# PuppyLight.net
KiCad netlist of a schematic drawn in Altium Designer
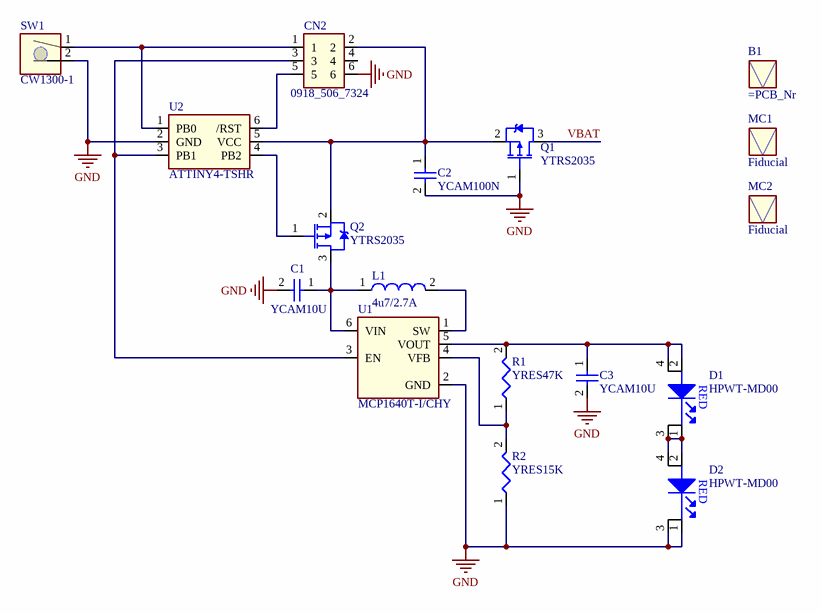
[diagram p0: PuppyLight.SchDoc]

(export (version "E")
  (design (tool "Eeschema 10.0.6"))
  (components
    (comp (ref "B1")
      (value "~")
      (footprint "MC_BoardNr")
      (fields (field (name "PART NUMBER") "BARE_PCB"))
      (libsource (lib "Testing") (part "BD_PCB"))
    )
    (comp (ref "C1") (value "YCAM10U") (footprint "CA_1206") (libsource (lib "Testing") (part "CA_NONPOL")))
    (comp (ref "C2") (value "YCAM100N") (footprint "CA_1206") (libsource (lib "Testing") (part "CA_NONPOL")))
    (comp (ref "C3") (value "YCAM10U") (footprint "CA_1206") (libsource (lib "Testing") (part "CA_NONPOL")))
    (comp (ref "CN2")
      (value "0918_506_7324")
      (footprint "CN_HARTING_918506X324")
      (fields (field (name "MANUFACTURER") "Harting"))
      (libsource (lib "Testing") (part "CN_2x3P"))
    )
    (comp (ref "D1")
      (value "HPWT-MD00")
      (footprint "DI_HPWT_Mx000-00000")
      (fields (field (name "MANUFACTURER") "Lumileds"))
      (libsource (lib "Testing") (part "DI_LED_RED_13_24"))
    )
    (comp (ref "D2")
      (value "HPWT-MD00")
      (footprint "DI_HPWT_Mx000-00000")
      (fields (field (name "MANUFACTURER") "Lumileds"))
      (libsource (lib "Testing") (part "DI_LED_RED_13_24"))
    )
    (comp (ref "L1")
      (value "4u7/2.7A")
      (footprint "CL_STD_2220")
      (fields (field (name "PART NUMBER") "LQH55DN4R7M03L") (field (name "MANUFACTURER") "Murata"))
      (libsource (lib "Testing") (part "CL_COIL"))
    )
    (comp (ref "MC1")
      (value "Fiducial")
      (footprint "MC_FIDUCIAL")
      (libsource (lib "Testing") (part "MC_MechPart_No_BOM"))
    )
    (comp (ref "MC2")
      (value "Fiducial")
      (footprint "MC_FIDUCIAL")
      (libsource (lib "Testing") (part "MC_MechPart_No_BOM"))
    )
    (comp (ref "Q1")
      (value "YTRS2035")
      (footprint "SC_SOT23")
      (fields (field (name "MANUFACTURER") "Diodes Inc."))
      (libsource (lib "Testing") (part "TR_PMOS"))
    )
    (comp (ref "Q2")
      (value "YTRS2035")
      (footprint "SC_SOT23")
      (fields (field (name "MANUFACTURER") "Diodes Inc."))
      (libsource (lib "Testing") (part "TR_PMOS"))
    )
    (comp (ref "R1")
      (value "YRES47K")
      (footprint "RE_1206")
      (description "Resistor")
      (fields (field (name "MANUFACTURER") "Vishay Draloric"))
      (libsource (lib "Testing") (part "RE_RES"))
    )
    (comp (ref "R2")
      (value "YRES15K")
      (footprint "RE_1206")
      (description "Resistor")
      (fields (field (name "MANUFACTURER") "Welwyn"))
      (libsource (lib "Testing") (part "RE_RES"))
    )
    (comp (ref "SW1")
      (value "CW1300-1")
      (footprint "SW_TILT_Comus_CW1300-1")
      (fields (field (name "MANUFACTURER") "Comus"))
      (libsource (lib "Testing") (part "SW_TILT"))
    )
    (comp (ref "U1")
      (value "MCP1640T-I/CHY")
      (footprint "SC_SOT23-6")
      (fields (field (name "MANUFACTURER") "Microchip"))
      (libsource (lib "Testing") (part "IC_MCP1640"))
    )
    (comp (ref "U2")
      (value "ATTINY4-TSHR")
      (footprint "SC_SOT23-6")
      (fields (field (name "MANUFACTURER") "Atmel"))
      (libsource (lib "Testing") (part "IC_ATMEL_ATTINY9"))
    )
  )
  (nets
    (net (code "1") (name "/VBAT") (class "Default")
      (node (ref "Q1") (pin "3") (pinfunction "D_3") (pintype "passive"))
    )
    (net (code "2") (name "GND") (class "Default")
      (node (ref "C1") (pin "2") (pinfunction "2_2") (pintype "passive"))
      (node (ref "C2") (pin "2") (pinfunction "2_2") (pintype "passive"))
      (node (ref "C3") (pin "2") (pinfunction "2_2") (pintype "passive"))
      (node (ref "CN2") (pin "6") (pinfunction "6_6") (pintype "passive"))
      (node (ref "D2") (pin "1") (pinfunction "C_1") (pintype "passive"))
      (node (ref "D2") (pin "3") (pinfunction "C_3") (pintype "passive"))
      (node (ref "Q1") (pin "1") (pinfunction "G_1") (pintype "passive"))
      (node (ref "R2") (pin "1") (pinfunction "1_1") (pintype "passive"))
      (node (ref "SW1") (pin "2") (pinfunction "2_2") (pintype "passive"))
      (node (ref "U1") (pin "2") (pinfunction "GND_2") (pintype "passive"))
      (node (ref "U2") (pin "2") (pinfunction "GND_2") (pintype "passive"))
    )
    (net (code "3") (name "Net-(D1-C-Pad1)") (class "Default")
      (node (ref "D1") (pin "1") (pinfunction "C_1") (pintype "passive"))
      (node (ref "D1") (pin "3") (pinfunction "C_3") (pintype "passive"))
      (node (ref "D2") (pin "2") (pinfunction "A_2") (pintype "passive"))
      (node (ref "D2") (pin "4") (pinfunction "A_4") (pintype "passive"))
    )
    (net (code "4") (name "Net-(Q1-S)") (class "Default")
      (node (ref "C2") (pin "1") (pinfunction "1_1") (pintype "passive"))
      (node (ref "CN2") (pin "2") (pinfunction "2_2") (pintype "passive"))
      (node (ref "Q1") (pin "2") (pinfunction "S_2") (pintype "passive"))
      (node (ref "Q2") (pin "2") (pinfunction "S_2") (pintype "passive"))
      (node (ref "U2") (pin "5") (pinfunction "VCC_5") (pintype "passive"))
    )
    (net (code "5") (name "Net-(Q2-D)") (class "Default")
      (node (ref "C1") (pin "1") (pinfunction "1_1") (pintype "passive"))
      (node (ref "L1") (pin "1") (pinfunction "1_1") (pintype "passive"))
      (node (ref "Q2") (pin "3") (pinfunction "D_3") (pintype "passive"))
      (node (ref "U1") (pin "6") (pinfunction "VIN_6") (pintype "passive"))
    )
    (net (code "6") (name "Net-(Q2-G)") (class "Default")
      (node (ref "Q2") (pin "1") (pinfunction "G_1") (pintype "passive"))
      (node (ref "U2") (pin "4") (pinfunction "PB2_4") (pintype "passive"))
    )
    (net (code "7") (name "Net-(U1-EN)") (class "Default")
      (node (ref "CN2") (pin "3") (pinfunction "3_3") (pintype "passive"))
      (node (ref "U1") (pin "3") (pinfunction "EN_3") (pintype "passive"))
      (node (ref "U2") (pin "3") (pinfunction "PB1_3") (pintype "passive"))
    )
    (net (code "8") (name "Net-(U1-SW)") (class "Default")
      (node (ref "L1") (pin "2") (pinfunction "2_2") (pintype "passive"))
      (node (ref "U1") (pin "1") (pinfunction "SW_1") (pintype "passive"))
    )
    (net (code "9") (name "Net-(U1-VFB)") (class "Default")
      (node (ref "R1") (pin "1") (pinfunction "1_1") (pintype "passive"))
      (node (ref "R2") (pin "2") (pinfunction "2_2") (pintype "passive"))
      (node (ref "U1") (pin "4") (pinfunction "VFB_4") (pintype "passive"))
    )
    (net (code "10") (name "Net-(U1-VOUT)") (class "Default")
      (node (ref "C3") (pin "1") (pinfunction "1_1") (pintype "passive"))
      (node (ref "D1") (pin "2") (pinfunction "A_2") (pintype "passive"))
      (node (ref "D1") (pin "4") (pinfunction "A_4") (pintype "passive"))
      (node (ref "R1") (pin "2") (pinfunction "2_2") (pintype "passive"))
      (node (ref "U1") (pin "5") (pinfunction "VOUT_5") (pintype "passive"))
    )
    (net (code "11") (name "Net-(U2-PB0)") (class "Default")
      (node (ref "CN2") (pin "1") (pinfunction "1_1") (pintype "passive"))
      (node (ref "SW1") (pin "1") (pinfunction "1_1") (pintype "passive"))
      (node (ref "U2") (pin "1") (pinfunction "PB0_1") (pintype "passive"))
    )
    (net (code "12") (name "Net-(U2-{slash}RST)") (class "Default")
      (node (ref "CN2") (pin "5") (pinfunction "5_5") (pintype "passive"))
      (node (ref "U2") (pin "6") (pinfunction "/RST_6") (pintype "passive"))
    )
    (net (code "13") (name "unconnected-(CN2-Pad4)") (class "Default")
      (node (ref "CN2") (pin "4") (pinfunction "4_4") (pintype "passive"))
    )
  )
)
